# TMC2160_BOB_V1_0.net
KiCad netlist of a schematic drawn in Altium Designer
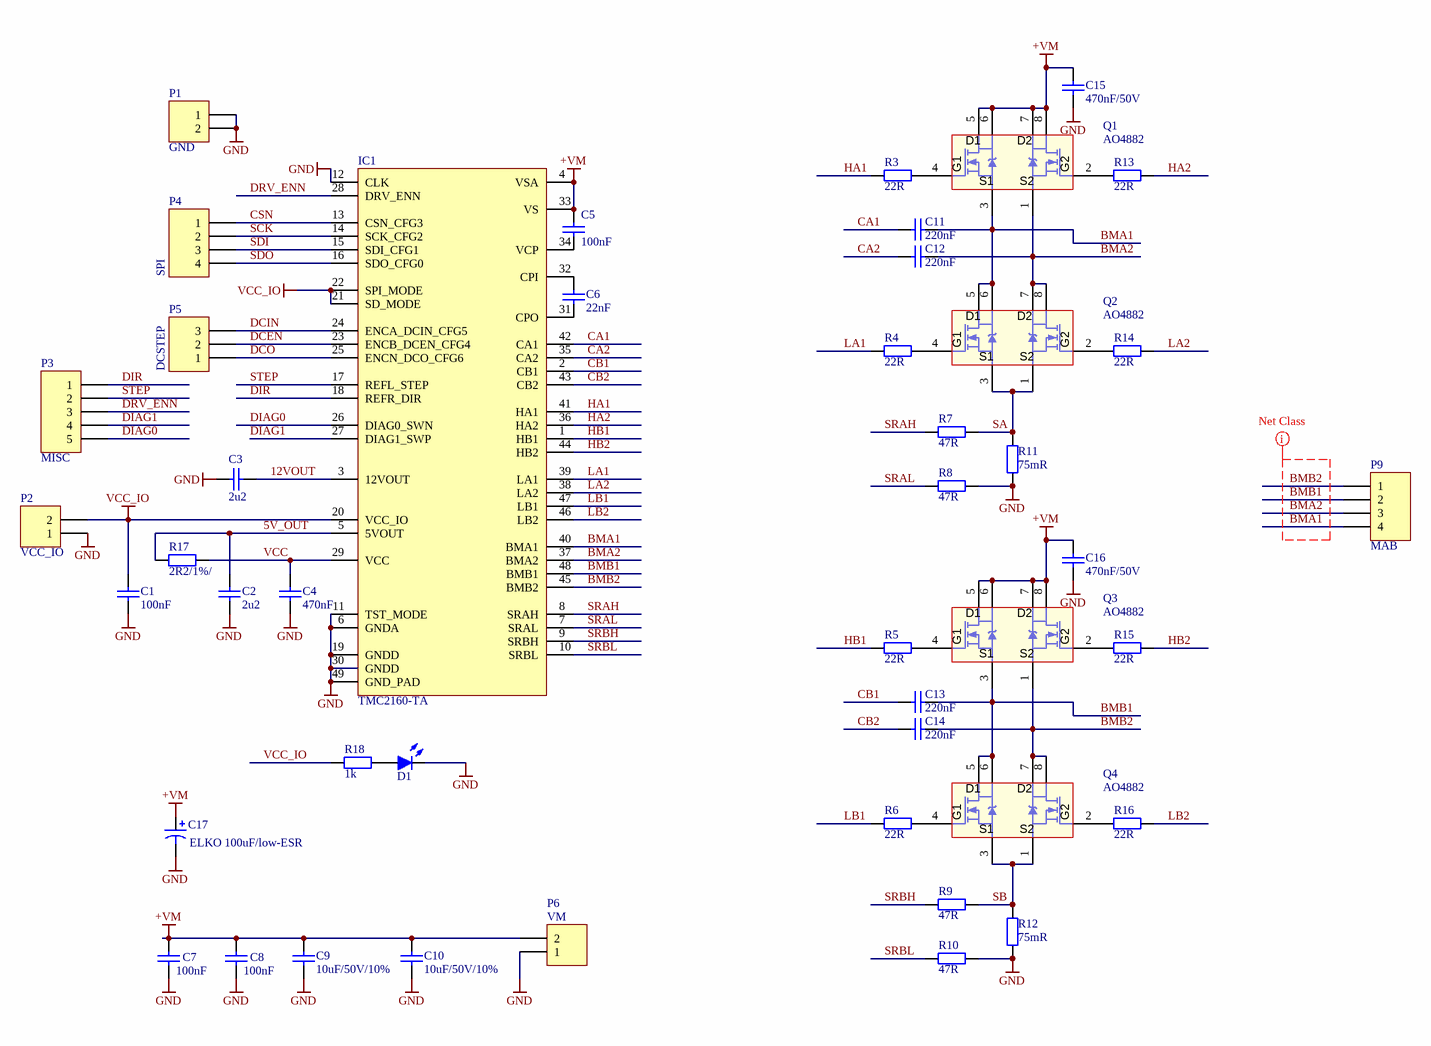
[diagram p0: TMC2160_BOB_V1_0.SchDoc]

(export (version "E")
  (design (tool "Eeschema 10.0.6"))
  (components
    (comp (ref "C1")
      (value "100nF")
      (footprint "C0603")
      (description "Ceramic capacitor")
      (fields (field (name "MF") "Multicomp") (field (name "MPN") "MC0603F104M500CT"))
      (libsource (lib "SCH Passives") (part "Capacitor"))
    )
    (comp (ref "C2")
      (value "2u2")
      (footprint "C0603")
      (description "SMD Multilayer Ceramic Capacitor, 0603 [1608 Metric], 2.2 µF, 25 V, ± 10%, X5R, GRM Series")
      (fields (field (name "MF") "MURATA") (field (name "MPN") "GRM188R61E225KA12D"))
      (libsource (lib "TMC5160_RevA") (part "2.2 µF, 25 V, ± 10%, X5R, GRM Series"))
    )
    (comp (ref "C3")
      (value "2u2")
      (footprint "C0603")
      (description "SMD Multilayer Ceramic Capacitor, 0603 [1608 Metric], 2.2 µF, 25 V, ± 10%, X5R, GRM Series")
      (fields (field (name "MF") "MURATA") (field (name "MPN") "GRM188R61E225KA12D"))
      (libsource (lib "TMC5160_RevA") (part "2.2 µF, 25 V, ± 10%, X5R, GRM Series"))
    )
    (comp (ref "C4")
      (value "470nF")
      (footprint "C0603")
      (description "Ceramic capacitor")
      (fields (field (name "MF") "Multicomp") (field (name "MPN") "MC0603X474K160CT"))
      (libsource (lib "SCH Passives") (part "Capacitor"))
    )
    (comp (ref "C5")
      (value "100nF")
      (footprint "C0603")
      (description "Ceramic capacitor")
      (fields (field (name "MF") "Multicomp") (field (name "MPN") "MC0603F104M500CT"))
      (libsource (lib "SCH Passives") (part "Capacitor"))
    )
    (comp (ref "C6")
      (value "22nF")
      (footprint "C0603")
      (description "Ceramic capacitor")
      (fields (field (name "MF") "Multicomp") (field (name "MPN") "MC0603B223K500CT"))
      (libsource (lib "SCH Passives") (part "Capacitor"))
    )
    (comp (ref "C7")
      (value "100nF")
      (footprint "C0603")
      (description "Ceramic capacitor")
      (fields (field (name "MANUFACTURER") "Multicomp") (field (name "MPN") "MC0603F104M500CT"))
      (libsource (lib "SCH Passives") (part "Capacitor"))
    )
    (comp (ref "C8")
      (value "100nF")
      (footprint "C0603")
      (description "Ceramic capacitor")
      (fields (field (name "MANUFACTURER") "Multicomp") (field (name "MPN") "MC0603F104M500CT"))
      (libsource (lib "SCH Passives") (part "Capacitor"))
    )
    (comp (ref "C9")
      (value "10uF/50V/10%")
      (footprint "C1206")
      (description "SMD Multilayer Ceramic Capacitor, 1206 [3216 Metric], 10 µF, 50 V, ± 20%, X5R, GRM Series")
      (fields (field (name "MF") "MURATA") (field (name "MPN") "GRM31CR61H106MA12L"))
      (libsource (lib "TMC262_FDD8424H_RevA") (part "10 µF, 50 V, ± 20%, X5R, GRM Series"))
    )
    (comp (ref "C10")
      (value "10uF/50V/10%")
      (footprint "C1206")
      (description "SMD Multilayer Ceramic Capacitor, 1206 [3216 Metric], 10 µF, 50 V, ± 20%, X5R, GRM Series")
      (fields (field (name "MF") "MURATA") (field (name "MPN") "GRM31CR61H106MA12L"))
      (libsource (lib "TMC262_FDD8424H_RevA") (part "10 µF, 50 V, ± 20%, X5R, GRM Series"))
    )
    (comp (ref "C11")
      (value "220nF")
      (footprint "C0603")
      (description "SMD Multilayer Ceramic Capacitor, 0603 [1608 Metric], 0.22 µF, 50 V, ± 10%, X7R, GCM Series")
      (fields (field (name "MF") "MURATA") (field (name "MPN") "GCM188R71H224KA64D"))
      (libsource (lib "TMC5160_RevA") (part "0.22 µF, 50 V, ± 10%, X7R"))
    )
    (comp (ref "C12")
      (value "220nF")
      (footprint "C0603")
      (description "SMD Multilayer Ceramic Capacitor, 0603 [1608 Metric], 0.22 µF, 50 V, ± 10%, X7R, GCM Series")
      (fields (field (name "MF") "MURATA") (field (name "MPN") "GCM188R71H224KA64D"))
      (libsource (lib "TMC5160_RevA") (part "0.22 µF, 50 V, ± 10%, X7R"))
    )
    (comp (ref "C13")
      (value "220nF")
      (footprint "C0603")
      (description "SMD Multilayer Ceramic Capacitor, 0603 [1608 Metric], 0.22 µF, 50 V, ± 10%, X7R, GCM Series")
      (fields (field (name "MF") "MURATA") (field (name "MPN") "GCM188R71H224KA64D"))
      (libsource (lib "TMC5160_RevA") (part "0.22 µF, 50 V, ± 10%, X7R"))
    )
    (comp (ref "C14")
      (value "220nF")
      (footprint "C0603")
      (description "SMD Multilayer Ceramic Capacitor, 0603 [1608 Metric], 0.22 µF, 50 V, ± 10%, X7R, GCM Series")
      (fields (field (name "MF") "MURATA") (field (name "MPN") "GCM188R71H224KA64D"))
      (libsource (lib "TMC5160_RevA") (part "0.22 µF, 50 V, ± 10%, X7R"))
    )
    (comp (ref "C15")
      (value "470nF/50V")
      (footprint "C0603")
      (description "SMD Multilayer Ceramic Capacitor, 0603 [1608 Metric], 0.47 µF, 50 V, ± 10%, X7R, C Series")
      (fields (field (name "MF") "TDK") (field (name "MPN") "C1608X7R1H474K080AC"))
      (libsource (lib "TMC5160_RevA") (part "0.47 µF, 50 V, ± 10%, X7R, C Series"))
    )
    (comp (ref "C16")
      (value "470nF/50V")
      (footprint "C0603")
      (description "SMD Multilayer Ceramic Capacitor, 0603 [1608 Metric], 0.47 µF, 50 V, ± 10%, X7R, C Series")
      (fields (field (name "MF") "TDK") (field (name "MPN") "C1608X7R1H474K080AC"))
      (libsource (lib "TMC5160_RevA") (part "0.47 µF, 50 V, ± 10%, X7R, C Series"))
    )
    (comp (ref "C17")
      (value "ELKO 100uF/low-ESR")
      (footprint "EXT_POL_CAP")
      (description "Polarized Capacitor (Radial)")
      (fields (field (name "Comment") "Cap Pol1") (field (name "PUBLISHER") "Altium Limited"))
      (libsource (lib "Miscellaneous Devices") (part "Cap Pol1"))
    )
    (comp (ref "D1")
      (value "LED, Blue, SMD, 20mA, 2.8V, 465 nm")
      (footprint "LED_0603")
      (fields (field (name "MF") "Lite-On") (field (name "MPN") "LTST-C191TBKT-5A"))
      (libsource (lib "TMC26x_RevA") (part "LED, Blue, SMD, 20mA, 2.8V, 465 nm"))
    )
    (comp (ref "IC1")
      (value "TMC2160-TA")
      (footprint "TMC5160_TSQFP50P900X900X120_HS-49L")
      (fields (field (name "MANUFACTURER") "TRINAMIC"))
      (libsource (lib "TMC2160_BOB_V1_0") (part "TMC2160-TA"))
    )
    (comp (ref "P1")
      (value "GND")
      (footprint "2_PIN_THT")
      (description "Header, 2-Pin")
      (fields (field (name "PUBLISHER") "Altium Limited"))
      (libsource (lib "") (part "Header 2_2"))
    )
    (comp (ref "P2")
      (value "VCC_IO")
      (footprint "2_PIN_THT")
      (description "Header, 2-Pin")
      (fields (field (name "PUBLISHER") "Altium Limited"))
      (libsource (lib "Miscellaneous Connectors") (part "Header 2"))
    )
    (comp (ref "P3")
      (value "MISC")
      (footprint "5_PIN_THT")
      (description "Header, 5-Pin")
      (fields (field (name "PUBLISHER") "Altium Limited"))
      (libsource (lib "Miscellaneous Connectors") (part "Header 5"))
    )
    (comp (ref "P4")
      (value "SPI")
      (footprint "4_PIN_THT")
      (description "Header, 4-Pin")
      (fields (field (name "PUBLISHER") "Altium Limited"))
      (libsource (lib "Miscellaneous Connectors") (part "Header 4"))
    )
    (comp (ref "P5")
      (value "DCSTEP")
      (footprint "3_PIN_THT")
      (description "Header, 3-Pin")
      (fields (field (name "PUBLISHER") "Altium Limited"))
      (libsource (lib "Miscellaneous Connectors") (part "Header 3"))
    )
    (comp (ref "P6")
      (value "VM")
      (footprint "2_PIN_THT")
      (description "Header, 2-Pin")
      (fields (field (name "PUBLISHER") "Altium Limited"))
      (libsource (lib "") (part "Header 2_1"))
    )
    (comp (ref "P9")
      (value "MAB")
      (footprint "4_PIN_THT_1mm_hole")
      (description "Wire-To-Board Connector, 2.5 mm, 4 Contacts, Header, EH Series, Through Hole, 1 Rows")
      (fields (field (name "MPN") "B4B-EH-A") (field (name "MF") "JST (JAPAN SOLDERLESS TERMINALS)"))
      (libsource (lib "TMC5160_RevA") (part "Wire-To-Board Connector, 2.5 mm, 4 Contacts, Header, EH Series, Through Hole, 1 Rows"))
    )
    (comp (ref "Q1")
      (value "AO4882")
      (footprint "SOP127P600X170-8L")
      (description "Mosfet Array 2 N-Channel (Dual) 40V 8A 2W Surface Mount 8-SOIC")
      (fields (field (name "MF") "Alpha & Omega Semiconductor Inc."))
      (libsource (lib "TMC5160_RevA") (part "AO4882 MOSFET 2N-CH 40V 8A 8SOIC"))
    )
    (comp (ref "Q2")
      (value "AO4882")
      (footprint "SOP127P600X170-8L")
      (description "Mosfet Array 2 N-Channel (Dual) 40V 8A 2W Surface Mount 8-SOIC")
      (fields (field (name "MF") "Alpha & Omega Semiconductor Inc."))
      (libsource (lib "TMC5160_RevA") (part "AO4882 MOSFET 2N-CH 40V 8A 8SOIC"))
    )
    (comp (ref "Q3")
      (value "AO4882")
      (footprint "SOP127P600X170-8L")
      (description "Mosfet Array 2 N-Channel (Dual) 40V 8A 2W Surface Mount 8-SOIC")
      (fields (field (name "MF") "Alpha & Omega Semiconductor Inc."))
      (libsource (lib "TMC5160_RevA") (part "AO4882 MOSFET 2N-CH 40V 8A 8SOIC"))
    )
    (comp (ref "Q4")
      (value "AO4882")
      (footprint "SOP127P600X170-8L")
      (description "Mosfet Array 2 N-Channel (Dual) 40V 8A 2W Surface Mount 8-SOIC")
      (fields (field (name "MF") "Alpha & Omega Semiconductor Inc."))
      (libsource (lib "TMC5160_RevA") (part "AO4882 MOSFET 2N-CH 40V 8A 8SOIC"))
    )
    (comp (ref "R3")
      (value "22R / 100mW / 1%")
      (footprint "R0603")
      (description "SMD Chip Resistor, Thick Film, 22 ohm, 50 V, 0603 [1608 Metric], 100 mW, ± 1%, MCWR Series")
      (fields
        (field (name "MPN") "MCWR06X22R0FTLV")
        (field (name "MF") "MULTICOMP")
        (field (name "RESISTANCE") "22R")
      )
      (libsource (lib "TMC5160_RevA") (part "22 ohm, 50 V, 0603 [1608 Metric], 100 mW, ± 1%, MCWR Series"))
    )
    (comp (ref "R4")
      (value "22R / 100mW / 1%")
      (footprint "R0603")
      (description "SMD Chip Resistor, Thick Film, 22 ohm, 50 V, 0603 [1608 Metric], 100 mW, ± 1%, MCWR Series")
      (fields
        (field (name "MPN") "MCWR06X22R0FTLV")
        (field (name "MF") "MULTICOMP")
        (field (name "RESISTANCE") "22R")
      )
      (libsource (lib "TMC5160_RevA") (part "22 ohm, 50 V, 0603 [1608 Metric], 100 mW, ± 1%, MCWR Series"))
    )
    (comp (ref "R5")
      (value "22R / 100mW / 1%")
      (footprint "R0603")
      (description "SMD Chip Resistor, Thick Film, 22 ohm, 50 V, 0603 [1608 Metric], 100 mW, ± 1%, MCWR Series")
      (fields
        (field (name "MPN") "MCWR06X22R0FTLV")
        (field (name "MF") "MULTICOMP")
        (field (name "RESISTANCE") "22R")
      )
      (libsource (lib "TMC5160_RevA") (part "22 ohm, 50 V, 0603 [1608 Metric], 100 mW, ± 1%, MCWR Series"))
    )
    (comp (ref "R6")
      (value "22R / 100mW / 1%")
      (footprint "R0603")
      (description "SMD Chip Resistor, Thick Film, 22 ohm, 50 V, 0603 [1608 Metric], 100 mW, ± 1%, MCWR Series")
      (fields
        (field (name "MPN") "MCWR06X22R0FTLV")
        (field (name "MF") "MULTICOMP")
        (field (name "RESISTANCE") "22R")
      )
      (libsource (lib "TMC5160_RevA") (part "22 ohm, 50 V, 0603 [1608 Metric], 100 mW, ± 1%, MCWR Series"))
    )
    (comp (ref "R7")
      (value "47R /  / 1%")
      (footprint "R0603")
      (description "SMD Chip Resistor, Ceramic, 47 ohm, 75 V, 0603 [1608 Metric], 100 mW, ± 1%, MCSR 06 Series")
      (fields
        (field (name "MPN") "MCSR06X47R0FTL")
        (field (name "MF") "MULTICOMP")
        (field (name "RESISTANCE") "47R")
      )
      (libsource (lib "TMC5160_RevA") (part "47 ohm, 75 V, 0603 [1608 Metric], 100 mW, ± 1%, MCSR 06 Series"))
    )
    (comp (ref "R8")
      (value "47R /  / 1%")
      (footprint "R0603")
      (description "SMD Chip Resistor, Ceramic, 47 ohm, 75 V, 0603 [1608 Metric], 100 mW, ± 1%, MCSR 06 Series")
      (fields
        (field (name "MPN") "MCSR06X47R0FTL")
        (field (name "MF") "MULTICOMP")
        (field (name "RESISTANCE") "47R")
      )
      (libsource (lib "TMC5160_RevA") (part "47 ohm, 75 V, 0603 [1608 Metric], 100 mW, ± 1%, MCSR 06 Series"))
    )
    (comp (ref "R9")
      (value "47R /  / 1%")
      (footprint "R0603")
      (description "SMD Chip Resistor, Ceramic, 47 ohm, 75 V, 0603 [1608 Metric], 100 mW, ± 1%, MCSR 06 Series")
      (fields
        (field (name "MPN") "MCSR06X47R0FTL")
        (field (name "MF") "MULTICOMP")
        (field (name "RESISTANCE") "47R")
      )
      (libsource (lib "TMC5160_RevA") (part "47 ohm, 75 V, 0603 [1608 Metric], 100 mW, ± 1%, MCSR 06 Series"))
    )
    (comp (ref "R10")
      (value "47R /  / 1%")
      (footprint "R0603")
      (description "SMD Chip Resistor, Ceramic, 47 ohm, 75 V, 0603 [1608 Metric], 100 mW, ± 1%, MCSR 06 Series")
      (fields
        (field (name "MPN") "MCSR06X47R0FTL")
        (field (name "MF") "MULTICOMP")
        (field (name "RESISTANCE") "47R")
      )
      (libsource (lib "TMC5160_RevA") (part "47 ohm, 75 V, 0603 [1608 Metric], 100 mW, ± 1%, MCSR 06 Series"))
    )
    (comp (ref "R11")
      (value "75mR")
      (footprint "R1206")
      (description "SMD Chip Resistor, Thick Film, Current Sense Resistors - SMD 1W 0.075ohm 1%")
      (fields
        (field (name "MPN") "ERJ-8BWFR075V")
        (field (name "MF") "Panasonic Electronic Components")
        (field (name "RESISTANCE") "75mR")
      )
      (libsource (lib "SMD_Passives") (part "R_SENS, 0.075 ohm, 1206, 1W, ± 1%, ERJ Series"))
    )
    (comp (ref "R12")
      (value "75mR")
      (footprint "R1206")
      (description "SMD Chip Resistor, Thick Film, Current Sense Resistors - SMD 1W 0.075ohm 1%")
      (fields
        (field (name "MPN") "ERJ-8BWFR075V")
        (field (name "MF") "Panasonic Electronic Components")
        (field (name "RESISTANCE") "75mR")
      )
      (libsource (lib "SMD_Passives") (part "R_SENS, 0.075 ohm, 1206, 1W, ± 1%, ERJ Series"))
    )
    (comp (ref "R13")
      (value "22R / 100mW / 1%")
      (footprint "R0603")
      (description "SMD Chip Resistor, Thick Film, 22 ohm, 50 V, 0603 [1608 Metric], 100 mW, ± 1%, MCWR Series")
      (fields
        (field (name "MPN") "MCWR06X22R0FTLV")
        (field (name "MF") "MULTICOMP")
        (field (name "RESISTANCE") "22R")
      )
      (libsource (lib "TMC5160_RevA") (part "22 ohm, 50 V, 0603 [1608 Metric], 100 mW, ± 1%, MCWR Series"))
    )
    (comp (ref "R14")
      (value "22R / 100mW / 1%")
      (footprint "R0603")
      (description "SMD Chip Resistor, Thick Film, 22 ohm, 50 V, 0603 [1608 Metric], 100 mW, ± 1%, MCWR Series")
      (fields
        (field (name "MPN") "MCWR06X22R0FTLV")
        (field (name "MF") "MULTICOMP")
        (field (name "RESISTANCE") "22R")
      )
      (libsource (lib "TMC5160_RevA") (part "22 ohm, 50 V, 0603 [1608 Metric], 100 mW, ± 1%, MCWR Series"))
    )
    (comp (ref "R15")
      (value "22R / 100mW / 1%")
      (footprint "R0603")
      (description "SMD Chip Resistor, Thick Film, 22 ohm, 50 V, 0603 [1608 Metric], 100 mW, ± 1%, MCWR Series")
      (fields
        (field (name "MPN") "MCWR06X22R0FTLV")
        (field (name "MF") "MULTICOMP")
        (field (name "RESISTANCE") "22R")
      )
      (libsource (lib "TMC5160_RevA") (part "22 ohm, 50 V, 0603 [1608 Metric], 100 mW, ± 1%, MCWR Series"))
    )
    (comp (ref "R16")
      (value "22R / 100mW / 1%")
      (footprint "R0603")
      (description "SMD Chip Resistor, Thick Film, 22 ohm, 50 V, 0603 [1608 Metric], 100 mW, ± 1%, MCWR Series")
      (fields
        (field (name "MPN") "MCWR06X22R0FTLV")
        (field (name "MF") "MULTICOMP")
        (field (name "RESISTANCE") "22R")
      )
      (libsource (lib "TMC5160_RevA") (part "22 ohm, 50 V, 0603 [1608 Metric], 100 mW, ± 1%, MCWR Series"))
    )
    (comp (ref "R17")
      (value "2R2/1%/")
      (footprint "R0603")
      (description "Resistor")
      (fields (field (name "MPN") "MC0063W060312R2") (field (name "MF") "Multicomp"))
      (libsource (lib "SCH Passives") (part "Resistor"))
    )
    (comp (ref "R18")
      (value "1k")
      (footprint "R0603")
      (description "1 kohm, 50 V, 0603 [1608 Metric], 63 mW, ± 1%, MC Series")
      (fields
        (field (name "MPN") "MC0063W060311K")
        (field (name "MF") "MULTICOMP")
        (field (name "RESISTANCE") "1k")
      )
      (libsource (lib "TMC457_RevA") (part "1 kohm, 50 V, 0603 [1608 Metric], 63 mW, ± 1%, MC Series"))
    )
  )
  (nets
    (net (code "1") (name "+VM") (class "Default")
      (node (ref "C10") (pin "2") (pinfunction "2_2") (pintype "passive"))
      (node (ref "C15") (pin "1") (pinfunction "1_1") (pintype "passive"))
      (node (ref "C16") (pin "1") (pinfunction "1_1") (pintype "passive"))
      (node (ref "C17") (pin "1") (pinfunction "1_1") (pintype "passive"))
      (node (ref "C5") (pin "1") (pinfunction "1_1") (pintype "passive"))
      (node (ref "C7") (pin "1") (pinfunction "1_1") (pintype "passive"))
      (node (ref "C8") (pin "1") (pinfunction "1_1") (pintype "passive"))
      (node (ref "C9") (pin "2") (pinfunction "2_2") (pintype "passive"))
      (node (ref "IC1") (pin "33") (pinfunction "VS_33") (pintype "passive"))
      (node (ref "IC1") (pin "4") (pinfunction "VSA_4") (pintype "passive"))
      (node (ref "P6") (pin "2") (pinfunction "2_2") (pintype "passive"))
      (node (ref "Q1") (pin "5") (pinfunction "D1_5") (pintype "passive"))
      (node (ref "Q1") (pin "6") (pinfunction "D1_6") (pintype "passive"))
      (node (ref "Q1") (pin "7") (pinfunction "D2_7") (pintype "passive"))
      (node (ref "Q1") (pin "8") (pinfunction "D2_8") (pintype "passive"))
      (node (ref "Q3") (pin "5") (pinfunction "D1_5") (pintype "passive"))
      (node (ref "Q3") (pin "6") (pinfunction "D1_6") (pintype "passive"))
      (node (ref "Q3") (pin "7") (pinfunction "D2_7") (pintype "passive"))
      (node (ref "Q3") (pin "8") (pinfunction "D2_8") (pintype "passive"))
    )
    (net (code "2") (name "/5V_OUT") (class "Default")
      (node (ref "C2") (pin "1") (pinfunction "1_1") (pintype "passive"))
      (node (ref "IC1") (pin "5") (pinfunction "5VOUT_5") (pintype "passive"))
      (node (ref "R17") (pin "1") (pinfunction "1_1") (pintype "passive"))
    )
    (net (code "3") (name "/12VOUT") (class "Default")
      (node (ref "C3") (pin "2") (pinfunction "2_2") (pintype "passive"))
      (node (ref "IC1") (pin "3") (pinfunction "12VOUT_3") (pintype "passive"))
    )
    (net (code "4") (name "/BMA1") (class "Default")
      (node (ref "C11") (pin "2") (pinfunction "2_2") (pintype "passive"))
      (node (ref "IC1") (pin "40") (pinfunction "BMA1_40") (pintype "passive"))
      (node (ref "P9") (pin "4") (pinfunction "4_4") (pintype "passive"))
      (node (ref "Q1") (pin "3") (pinfunction "S1_3") (pintype "passive"))
      (node (ref "Q2") (pin "5") (pinfunction "D1_5") (pintype "passive"))
      (node (ref "Q2") (pin "6") (pinfunction "D1_6") (pintype "passive"))
    )
    (net (code "5") (name "/BMA2") (class "Default")
      (node (ref "C12") (pin "2") (pinfunction "2_2") (pintype "passive"))
      (node (ref "IC1") (pin "37") (pinfunction "BMA2_37") (pintype "passive"))
      (node (ref "P9") (pin "3") (pinfunction "3_3") (pintype "passive"))
      (node (ref "Q1") (pin "1") (pinfunction "S2_1") (pintype "passive"))
      (node (ref "Q2") (pin "7") (pinfunction "D2_7") (pintype "passive"))
      (node (ref "Q2") (pin "8") (pinfunction "D2_8") (pintype "passive"))
    )
    (net (code "6") (name "/BMB1") (class "Default")
      (node (ref "C13") (pin "2") (pinfunction "2_2") (pintype "passive"))
      (node (ref "IC1") (pin "48") (pinfunction "BMB1_48") (pintype "passive"))
      (node (ref "P9") (pin "2") (pinfunction "2_2") (pintype "passive"))
      (node (ref "Q3") (pin "3") (pinfunction "S1_3") (pintype "passive"))
      (node (ref "Q4") (pin "5") (pinfunction "D1_5") (pintype "passive"))
      (node (ref "Q4") (pin "6") (pinfunction "D1_6") (pintype "passive"))
    )
    (net (code "7") (name "/BMB2") (class "Default")
      (node (ref "C14") (pin "2") (pinfunction "2_2") (pintype "passive"))
      (node (ref "IC1") (pin "45") (pinfunction "BMB2_45") (pintype "passive"))
      (node (ref "P9") (pin "1") (pinfunction "1_1") (pintype "passive"))
      (node (ref "Q3") (pin "1") (pinfunction "S2_1") (pintype "passive"))
      (node (ref "Q4") (pin "7") (pinfunction "D2_7") (pintype "passive"))
      (node (ref "Q4") (pin "8") (pinfunction "D2_8") (pintype "passive"))
    )
    (net (code "8") (name "/CA1") (class "Default")
      (node (ref "C11") (pin "1") (pinfunction "1_1") (pintype "passive"))
      (node (ref "IC1") (pin "42") (pinfunction "CA1_42") (pintype "passive"))
    )
    (net (code "9") (name "/CA2") (class "Default")
      (node (ref "C12") (pin "1") (pinfunction "1_1") (pintype "passive"))
      (node (ref "IC1") (pin "35") (pinfunction "CA2_35") (pintype "passive"))
    )
    (net (code "10") (name "/CB1") (class "Default")
      (node (ref "C13") (pin "1") (pinfunction "1_1") (pintype "passive"))
      (node (ref "IC1") (pin "2") (pinfunction "CB1_2") (pintype "passive"))
    )
    (net (code "11") (name "/CB2") (class "Default")
      (node (ref "C14") (pin "1") (pinfunction "1_1") (pintype "passive"))
      (node (ref "IC1") (pin "43") (pinfunction "CB2_43") (pintype "passive"))
    )
    (net (code "12") (name "/CSN") (class "Default")
      (node (ref "IC1") (pin "13") (pinfunction "CSN_CFG3_13") (pintype "passive"))
      (node (ref "P4") (pin "1") (pinfunction "1_1") (pintype "passive"))
    )
    (net (code "13") (name "/DCEN") (class "Default")
      (node (ref "IC1") (pin "23") (pinfunction "ENCB_DCEN_CFG4_23") (pintype "passive"))
      (node (ref "P5") (pin "2") (pinfunction "2_2") (pintype "passive"))
    )
    (net (code "14") (name "/DCIN") (class "Default")
      (node (ref "IC1") (pin "24") (pinfunction "ENCA_DCIN_CFG5_24") (pintype "passive"))
      (node (ref "P5") (pin "3") (pinfunction "3_3") (pintype "passive"))
    )
    (net (code "15") (name "/DCO") (class "Default")
      (node (ref "IC1") (pin "25") (pinfunction "ENCN_DCO_CFG6_25") (pintype "passive"))
      (node (ref "P5") (pin "1") (pinfunction "1_1") (pintype "passive"))
    )
    (net (code "16") (name "/DIAG0") (class "Default")
      (node (ref "IC1") (pin "26") (pinfunction "DIAG0_SWN_26") (pintype "passive"))
      (node (ref "P3") (pin "5") (pinfunction "5_5") (pintype "passive"))
    )
    (net (code "17") (name "/DIAG1") (class "Default")
      (node (ref "IC1") (pin "27") (pinfunction "DIAG1_SWP_27") (pintype "passive"))
      (node (ref "P3") (pin "4") (pinfunction "4_4") (pintype "passive"))
    )
    (net (code "18") (name "/DIR") (class "Default")
      (node (ref "IC1") (pin "18") (pinfunction "REFR_DIR_18") (pintype "passive"))
      (node (ref "P3") (pin "1") (pinfunction "1_1") (pintype "passive"))
    )
    (net (code "19") (name "/DRV_ENN") (class "Default")
      (node (ref "IC1") (pin "28") (pinfunction "DRV_ENN_28") (pintype "passive"))
      (node (ref "P3") (pin "3") (pinfunction "3_3") (pintype "passive"))
    )
    (net (code "20") (name "/HA1") (class "Default")
      (node (ref "IC1") (pin "41") (pinfunction "HA1_41") (pintype "passive"))
      (node (ref "R3") (pin "2") (pinfunction "2_2") (pintype "passive"))
    )
    (net (code "21") (name "/HA2") (class "Default")
      (node (ref "IC1") (pin "36") (pinfunction "HA2_36") (pintype "passive"))
      (node (ref "R13") (pin "1") (pinfunction "1_1") (pintype "passive"))
    )
    (net (code "22") (name "/HB1") (class "Default")
      (node (ref "IC1") (pin "1") (pinfunction "HB1_1") (pintype "passive"))
      (node (ref "R5") (pin "2") (pinfunction "2_2") (pintype "passive"))
    )
    (net (code "23") (name "/HB2") (class "Default")
      (node (ref "IC1") (pin "44") (pinfunction "HB2_44") (pintype "passive"))
      (node (ref "R15") (pin "1") (pinfunction "1_1") (pintype "passive"))
    )
    (net (code "24") (name "/LA1") (class "Default")
      (node (ref "IC1") (pin "39") (pinfunction "LA1_39") (pintype "passive"))
      (node (ref "R4") (pin "2") (pinfunction "2_2") (pintype "passive"))
    )
    (net (code "25") (name "/LA2") (class "Default")
      (node (ref "IC1") (pin "38") (pinfunction "LA2_38") (pintype "passive"))
      (node (ref "R14") (pin "1") (pinfunction "1_1") (pintype "passive"))
    )
    (net (code "26") (name "/LB1") (class "Default")
      (node (ref "IC1") (pin "47") (pinfunction "LB1_47") (pintype "passive"))
      (node (ref "R6") (pin "2") (pinfunction "2_2") (pintype "passive"))
    )
    (net (code "27") (name "/LB2") (class "Default")
      (node (ref "IC1") (pin "46") (pinfunction "LB2_46") (pintype "passive"))
      (node (ref "R16") (pin "1") (pinfunction "1_1") (pintype "passive"))
    )
    (net (code "28") (name "/SA") (class "Default")
      (node (ref "Q2") (pin "1") (pinfunction "S2_1") (pintype "passive"))
      (node (ref "Q2") (pin "3") (pinfunction "S1_3") (pintype "passive"))
      (node (ref "R11") (pin "1") (pinfunction "1_1") (pintype "passive"))
      (node (ref "R7") (pin "1") (pinfunction "1_1") (pintype "passive"))
    )
    (net (code "29") (name "/SB") (class "Default")
      (node (ref "Q4") (pin "1") (pinfunction "S2_1") (pintype "passive"))
      (node (ref "Q4") (pin "3") (pinfunction "S1_3") (pintype "passive"))
      (node (ref "R12") (pin "1") (pinfunction "1_1") (pintype "passive"))
      (node (ref "R9") (pin "1") (pinfunction "1_1") (pintype "passive"))
    )
    (net (code "30") (name "/SCK") (class "Default")
      (node (ref "IC1") (pin "14") (pinfunction "SCK_CFG2_14") (pintype "passive"))
      (node (ref "P4") (pin "2") (pinfunction "2_2") (pintype "passive"))
    )
    (net (code "31") (name "/SDI") (class "Default")
      (node (ref "IC1") (pin "15") (pinfunction "SDI_CFG1_15") (pintype "passive"))
      (node (ref "P4") (pin "3") (pinfunction "3_3") (pintype "passive"))
    )
    (net (code "32") (name "/SDO") (class "Default")
      (node (ref "IC1") (pin "16") (pinfunction "SDO_CFG0_16") (pintype "passive"))
      (node (ref "P4") (pin "4") (pinfunction "4_4") (pintype "passive"))
    )
    (net (code "33") (name "/SRAH") (class "Default")
      (node (ref "IC1") (pin "8") (pinfunction "SRAH_8") (pintype "passive"))
      (node (ref "R7") (pin "2") (pinfunction "2_2") (pintype "passive"))
    )
    (net (code "34") (name "/SRAL") (class "Default")
      (node (ref "IC1") (pin "7") (pinfunction "SRAL_7") (pintype "passive"))
      (node (ref "R8") (pin "2") (pinfunction "2_2") (pintype "passive"))
    )
    (net (code "35") (name "/SRBH") (class "Default")
      (node (ref "IC1") (pin "9") (pinfunction "SRBH_9") (pintype "passive"))
      (node (ref "R9") (pin "2") (pinfunction "2_2") (pintype "passive"))
    )
    (net (code "36") (name "/SRBL") (class "Default")
      (node (ref "IC1") (pin "10") (pinfunction "SRBL_10") (pintype "passive"))
      (node (ref "R10") (pin "2") (pinfunction "2_2") (pintype "passive"))
    )
    (net (code "37") (name "/STEP") (class "Default")
      (node (ref "IC1") (pin "17") (pinfunction "REFL_STEP_17") (pintype "passive"))
      (node (ref "P3") (pin "2") (pinfunction "2_2") (pintype "passive"))
    )
    (net (code "38") (name "/VCC") (class "Default")
      (node (ref "C4") (pin "1") (pinfunction "1_1") (pintype "passive"))
      (node (ref "IC1") (pin "29") (pinfunction "VCC_29") (pintype "passive"))
      (node (ref "R17") (pin "2") (pinfunction "2_2") (pintype "passive"))
    )
    (net (code "39") (name "GND") (class "Default")
      (node (ref "C1") (pin "2") (pinfunction "2_2") (pintype "passive"))
      (node (ref "C10") (pin "1") (pinfunction "1_1") (pintype "passive"))
      (node (ref "C15") (pin "2") (pinfunction "2_2") (pintype "passive"))
      (node (ref "C16") (pin "2") (pinfunction "2_2") (pintype "passive"))
      (node (ref "C17") (pin "2") (pinfunction "2_2") (pintype "passive"))
      (node (ref "C2") (pin "2") (pinfunction "2_2") (pintype "passive"))
      (node (ref "C3") (pin "1") (pinfunction "1_1") (pintype "passive"))
      (node (ref "C4") (pin "2") (pinfunction "2_2") (pintype "passive"))
      (node (ref "C7") (pin "2") (pinfunction "2_2") (pintype "passive"))
      (node (ref "C8") (pin "2") (pinfunction "2_2") (pintype "passive"))
      (node (ref "C9") (pin "1") (pinfunction "1_1") (pintype "passive"))
      (node (ref "D1") (pin "2") (pinfunction "K_2") (pintype "passive"))
      (node (ref "IC1") (pin "11") (pinfunction "TST_MODE_11") (pintype "passive"))
      (node (ref "IC1") (pin "12") (pinfunction "CLK_12") (pintype "passive"))
      (node (ref "IC1") (pin "19") (pinfunction "GNDD_19") (pintype "passive"))
      (node (ref "IC1") (pin "30") (pinfunction "GNDD_30") (pintype "passive"))
      (node (ref "IC1") (pin "49") (pinfunction "GND_PAD_49") (pintype "passive"))
      (node (ref "IC1") (pin "6") (pinfunction "GNDA_6") (pintype "passive"))
      (node (ref "P1") (pin "1") (pinfunction "1_1") (pintype "passive"))
      (node (ref "P1") (pin "2") (pinfunction "2_2") (pintype "passive"))
      (node (ref "P2") (pin "1") (pinfunction "1_1") (pintype "passive"))
      (node (ref "P6") (pin "1") (pinfunction "1_1") (pintype "passive"))
      (node (ref "R10") (pin "1") (pinfunction "1_1") (pintype "passive"))
      (node (ref "R11") (pin "2") (pinfunction "2_2") (pintype "passive"))
      (node (ref "R12") (pin "2") (pinfunction "2_2") (pintype "passive"))
      (node (ref "R8") (pin "1") (pinfunction "1_1") (pintype "passive"))
    )
    (net (code "40") (name "Net-(D1-A)") (class "Default")
      (node (ref "D1") (pin "1") (pinfunction "A_1") (pintype "passive"))
      (node (ref "R18") (pin "2") (pinfunction "2_2") (pintype "passive"))
    )
    (net (code "41") (name "Net-(IC1-CPI)") (class "Default")
      (node (ref "C6") (pin "2") (pinfunction "2_2") (pintype "passive"))
      (node (ref "IC1") (pin "32") (pinfunction "CPI_32") (pintype "passive"))
    )
    (net (code "42") (name "Net-(IC1-CPO)") (class "Default")
      (node (ref "C6") (pin "1") (pinfunction "1_1") (pintype "passive"))
      (node (ref "IC1") (pin "31") (pinfunction "CPO_31") (pintype "passive"))
    )
    (net (code "43") (name "Net-(IC1-VCP)") (class "Default")
      (node (ref "C5") (pin "2") (pinfunction "2_2") (pintype "passive"))
      (node (ref "IC1") (pin "34") (pinfunction "VCP_34") (pintype "passive"))
    )
    (net (code "44") (name "Net-(Q1-G1)") (class "Default")
      (node (ref "Q1") (pin "4") (pinfunction "G1_4") (pintype "passive"))
      (node (ref "R3") (pin "1") (pinfunction "1_1") (pintype "passive"))
    )
    (net (code "45") (name "Net-(Q1-G2)") (class "Default")
      (node (ref "Q1") (pin "2") (pinfunction "G2_2") (pintype "passive"))
      (node (ref "R13") (pin "2") (pinfunction "2_2") (pintype "passive"))
    )
    (net (code "46") (name "Net-(Q2-G1)") (class "Default")
      (node (ref "Q2") (pin "4") (pinfunction "G1_4") (pintype "passive"))
      (node (ref "R4") (pin "1") (pinfunction "1_1") (pintype "passive"))
    )
    (net (code "47") (name "Net-(Q2-G2)") (class "Default")
      (node (ref "Q2") (pin "2") (pinfunction "G2_2") (pintype "passive"))
      (node (ref "R14") (pin "2") (pinfunction "2_2") (pintype "passive"))
    )
    (net (code "48") (name "Net-(Q3-G1)") (class "Default")
      (node (ref "Q3") (pin "4") (pinfunction "G1_4") (pintype "passive"))
      (node (ref "R5") (pin "1") (pinfunction "1_1") (pintype "passive"))
    )
    (net (code "49") (name "Net-(Q3-G2)") (class "Default")
      (node (ref "Q3") (pin "2") (pinfunction "G2_2") (pintype "passive"))
      (node (ref "R15") (pin "2") (pinfunction "2_2") (pintype "passive"))
    )
    (net (code "50") (name "Net-(Q4-G1)") (class "Default")
      (node (ref "Q4") (pin "4") (pinfunction "G1_4") (pintype "passive"))
      (node (ref "R6") (pin "1") (pinfunction "1_1") (pintype "passive"))
    )
    (net (code "51") (name "Net-(Q4-G2)") (class "Default")
      (node (ref "Q4") (pin "2") (pinfunction "G2_2") (pintype "passive"))
      (node (ref "R16") (pin "2") (pinfunction "2_2") (pintype "passive"))
    )
    (net (code "52") (name "VCC_IO") (class "Default")
      (node (ref "C1") (pin "1") (pinfunction "1_1") (pintype "passive"))
      (node (ref "IC1") (pin "20") (pinfunction "VCC_IO_20") (pintype "passive"))
      (node (ref "IC1") (pin "21") (pinfunction "SD_MODE_21") (pintype "passive"))
      (node (ref "IC1") (pin "22") (pinfunction "SPI_MODE_22") (pintype "passive"))
      (node (ref "P2") (pin "2") (pinfunction "2_2") (pintype "passive"))
      (node (ref "R18") (pin "1") (pinfunction "1_1") (pintype "passive"))
    )
  )
)
